# dimitar-schematic.net
KiCad netlist of a schematic drawn in EAGLE
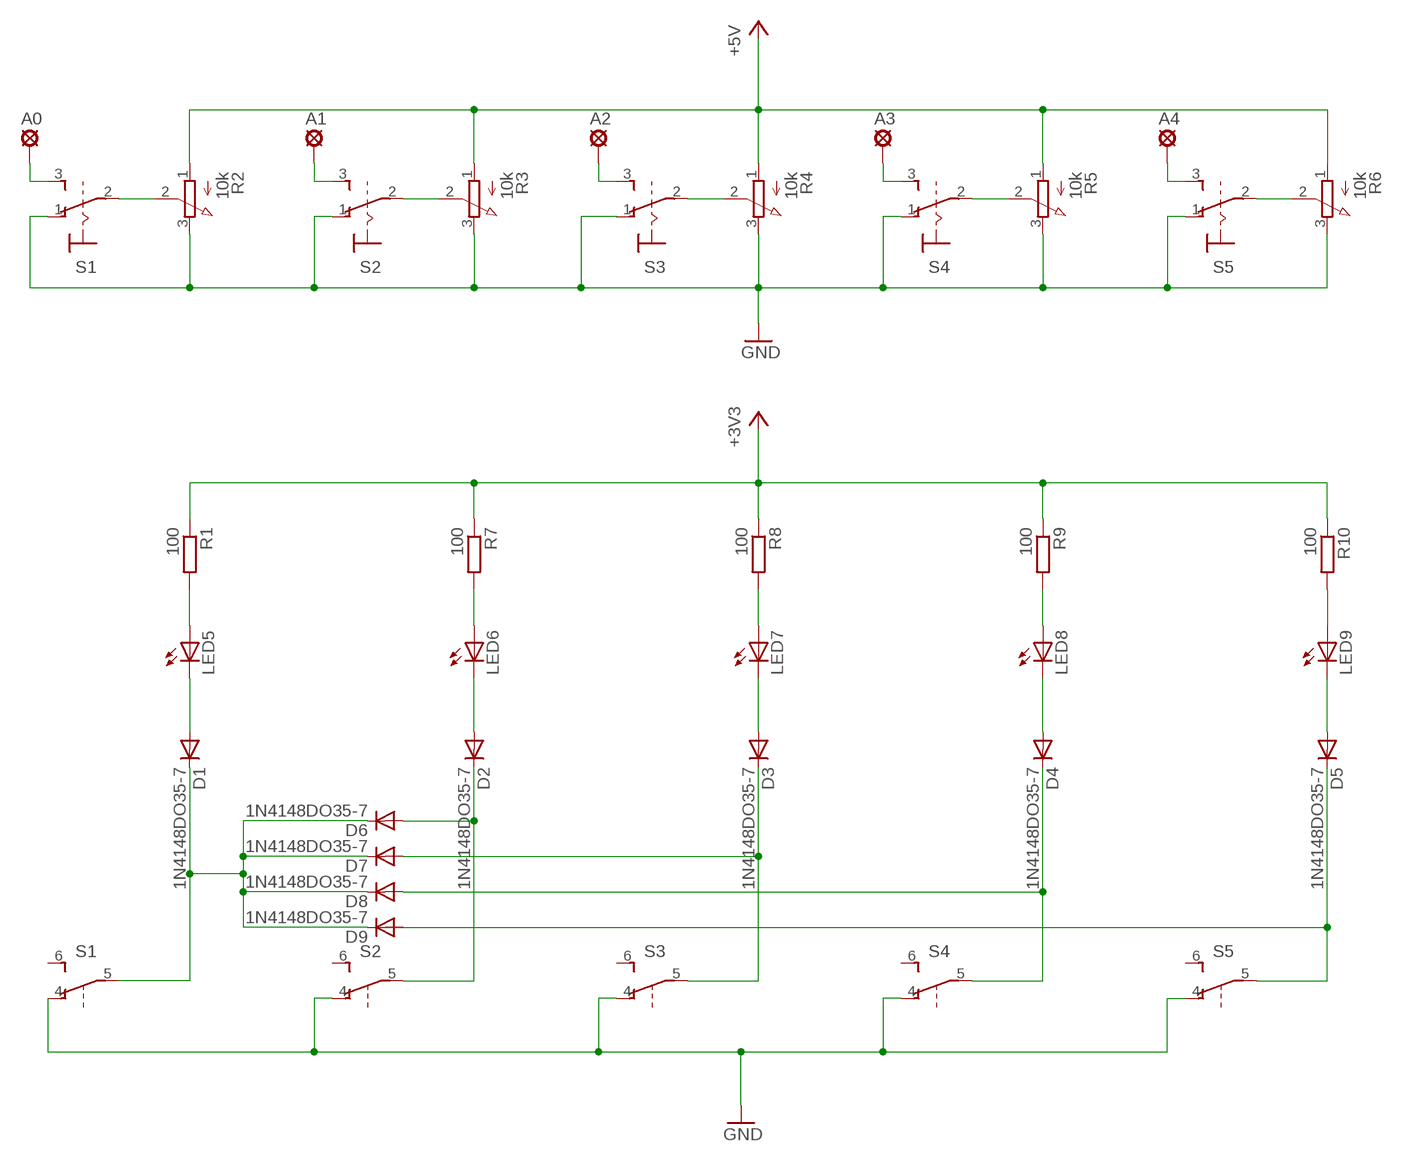
[diagram p0: schematic, sheet 1]

(export (version "E")
  (design (tool "Eeschema 10.0.6"))
  (components
    (comp (ref "A0")
      (value "SE14")
      (footprint "eagle-import:SE14")
      (libsource (lib "eagle-import") (part "SE14"))
    )
    (comp (ref "A1")
      (value "SE14")
      (footprint "eagle-import:SE14")
      (libsource (lib "eagle-import") (part "SE14"))
    )
    (comp (ref "A2")
      (value "SE14")
      (footprint "eagle-import:SE14")
      (libsource (lib "eagle-import") (part "SE14"))
    )
    (comp (ref "A3")
      (value "SE14")
      (footprint "eagle-import:SE14")
      (libsource (lib "eagle-import") (part "SE14"))
    )
    (comp (ref "A4")
      (value "SE14")
      (footprint "eagle-import:SE14")
      (libsource (lib "eagle-import") (part "SE14"))
    )
    (comp (ref "D1")
      (value "1N4148DO35-7")
      (footprint "eagle-import:DO35-7")
      (libsource (lib "eagle-import") (part "1N4148DO35-7"))
    )
    (comp (ref "D2")
      (value "1N4148DO35-7")
      (footprint "eagle-import:DO35-7")
      (libsource (lib "eagle-import") (part "1N4148DO35-7"))
    )
    (comp (ref "D3")
      (value "1N4148DO35-7")
      (footprint "eagle-import:DO35-7")
      (libsource (lib "eagle-import") (part "1N4148DO35-7"))
    )
    (comp (ref "D4")
      (value "1N4148DO35-7")
      (footprint "eagle-import:DO35-7")
      (libsource (lib "eagle-import") (part "1N4148DO35-7"))
    )
    (comp (ref "D5")
      (value "1N4148DO35-7")
      (footprint "eagle-import:DO35-7")
      (libsource (lib "eagle-import") (part "1N4148DO35-7"))
    )
    (comp (ref "D6")
      (value "1N4148DO35-7")
      (footprint "eagle-import:DO35-7")
      (libsource (lib "eagle-import") (part "1N4148DO35-7"))
    )
    (comp (ref "D7")
      (value "1N4148DO35-7")
      (footprint "eagle-import:DO35-7")
      (libsource (lib "eagle-import") (part "1N4148DO35-7"))
    )
    (comp (ref "D8")
      (value "1N4148DO35-7")
      (footprint "eagle-import:DO35-7")
      (libsource (lib "eagle-import") (part "1N4148DO35-7"))
    )
    (comp (ref "D9")
      (value "1N4148DO35-7")
      (footprint "eagle-import:DO35-7")
      (libsource (lib "eagle-import") (part "1N4148DO35-7"))
    )
    (comp (ref "LED5")
      (value "LED5MM")
      (footprint "eagle-import:LED5MM")
      (libsource (lib "eagle-import") (part "LED5MM"))
    )
    (comp (ref "LED6")
      (value "LED5MM")
      (footprint "eagle-import:LED5MM")
      (libsource (lib "eagle-import") (part "LED5MM"))
    )
    (comp (ref "LED7")
      (value "LED5MM")
      (footprint "eagle-import:LED5MM")
      (libsource (lib "eagle-import") (part "LED5MM"))
    )
    (comp (ref "LED8")
      (value "LED5MM")
      (footprint "eagle-import:LED5MM")
      (libsource (lib "eagle-import") (part "LED5MM"))
    )
    (comp (ref "LED9")
      (value "LED5MM")
      (footprint "eagle-import:LED5MM")
      (libsource (lib "eagle-import") (part "LED5MM"))
    )
    (comp (ref "R1")
      (value "100")
      (footprint "eagle-import:0207_10")
      (libsource (lib "eagle-import") (part "R0207/10"))
    )
    (comp (ref "R2")
      (value "10k")
      (footprint "eagle-import:3RP_1610N")
      (libsource (lib "eagle-import") (part "3RP/1610N"))
    )
    (comp (ref "R3")
      (value "10k")
      (footprint "eagle-import:3RP_1610N")
      (libsource (lib "eagle-import") (part "3RP/1610N"))
    )
    (comp (ref "R4")
      (value "10k")
      (footprint "eagle-import:3RP_1610N")
      (libsource (lib "eagle-import") (part "3RP/1610N"))
    )
    (comp (ref "R5")
      (value "10k")
      (footprint "eagle-import:3RP_1610N")
      (libsource (lib "eagle-import") (part "3RP/1610N"))
    )
    (comp (ref "R6")
      (value "10k")
      (footprint "eagle-import:3RP_1610N")
      (libsource (lib "eagle-import") (part "3RP/1610N"))
    )
    (comp (ref "R7")
      (value "100")
      (footprint "eagle-import:0207_10")
      (libsource (lib "eagle-import") (part "R0207/10"))
    )
    (comp (ref "R8")
      (value "100")
      (footprint "eagle-import:0207_10")
      (libsource (lib "eagle-import") (part "R0207/10"))
    )
    (comp (ref "R9")
      (value "100")
      (footprint "eagle-import:0207_10")
      (libsource (lib "eagle-import") (part "R0207/10"))
    )
    (comp (ref "R10")
      (value "100")
      (footprint "eagle-import:0207_10")
      (libsource (lib "eagle-import") (part "R0207/10"))
    )
    (comp (ref "S1")
      (value "320-938")
      (footprint "eagle-import:320-938")
      (libsource (lib "eagle-import") (part "320-938"))
    )
    (comp (ref "S2")
      (value "320-938")
      (footprint "eagle-import:320-938")
      (libsource (lib "eagle-import") (part "320-938"))
    )
    (comp (ref "S3")
      (value "320-938")
      (footprint "eagle-import:320-938")
      (libsource (lib "eagle-import") (part "320-938"))
    )
    (comp (ref "S4")
      (value "320-938")
      (footprint "eagle-import:320-938")
      (libsource (lib "eagle-import") (part "320-938"))
    )
    (comp (ref "S5")
      (value "320-938")
      (footprint "eagle-import:320-938")
      (libsource (lib "eagle-import") (part "320-938"))
    )
  )
  (nets
    (net (code "1") (name "+3V3") (class "Default")
      (node (ref "R1") (pin "1") (pinfunction "1_1") (pintype "passive"))
      (node (ref "R10") (pin "1") (pinfunction "1_1") (pintype "passive"))
      (node (ref "R7") (pin "1") (pinfunction "1_1") (pintype "passive"))
      (node (ref "R8") (pin "1") (pinfunction "1_1") (pintype "passive"))
      (node (ref "R9") (pin "1") (pinfunction "1_1") (pintype "passive"))
    )
    (net (code "2") (name "+5V") (class "Default")
      (node (ref "R2") (pin "1") (pinfunction "A_1") (pintype "passive"))
      (node (ref "R3") (pin "1") (pinfunction "A_1") (pintype "passive"))
      (node (ref "R4") (pin "1") (pinfunction "A_1") (pintype "passive"))
      (node (ref "R5") (pin "1") (pinfunction "A_1") (pintype "passive"))
      (node (ref "R6") (pin "1") (pinfunction "A_1") (pintype "passive"))
    )
    (net (code "3") (name "GND") (class "Default")
      (node (ref "R2") (pin "3") (pinfunction "E_3") (pintype "passive"))
      (node (ref "R3") (pin "3") (pinfunction "E_3") (pintype "passive"))
      (node (ref "R4") (pin "3") (pinfunction "E_3") (pintype "passive"))
      (node (ref "R5") (pin "3") (pinfunction "E_3") (pintype "passive"))
      (node (ref "R6") (pin "3") (pinfunction "E_3") (pintype "passive"))
      (node (ref "S1") (pin "1") (pinfunction "O_1") (pintype "passive"))
      (node (ref "S1") (pin "4") (pinfunction "O_4") (pintype "passive"))
      (node (ref "S2") (pin "1") (pinfunction "O_1") (pintype "passive"))
      (node (ref "S2") (pin "4") (pinfunction "O_4") (pintype "passive"))
      (node (ref "S3") (pin "1") (pinfunction "O_1") (pintype "passive"))
      (node (ref "S3") (pin "4") (pinfunction "O_4") (pintype "passive"))
      (node (ref "S4") (pin "1") (pinfunction "O_1") (pintype "passive"))
      (node (ref "S4") (pin "4") (pinfunction "O_4") (pintype "passive"))
      (node (ref "S5") (pin "1") (pinfunction "O_1") (pintype "passive"))
      (node (ref "S5") (pin "4") (pinfunction "O_4") (pintype "passive"))
    )
    (net (code "4") (name "Net-(LED5-C)") (class "Default")
      (node (ref "D1") (pin "A") (pinfunction "A_A") (pintype "passive"))
      (node (ref "LED5") (pin "K") (pinfunction "C_K") (pintype "passive"))
    )
    (net (code "5") (name "Net-(LED5-PadA)") (class "Default")
      (node (ref "LED5") (pin "A") (pinfunction "A_A") (pintype "passive"))
      (node (ref "R1") (pin "2") (pinfunction "2_2") (pintype "passive"))
    )
    (net (code "6") (name "Net-(LED6-C)") (class "Default")
      (node (ref "D2") (pin "A") (pinfunction "A_A") (pintype "passive"))
      (node (ref "LED6") (pin "K") (pinfunction "C_K") (pintype "passive"))
    )
    (net (code "7") (name "Net-(LED6-PadA)") (class "Default")
      (node (ref "LED6") (pin "A") (pinfunction "A_A") (pintype "passive"))
      (node (ref "R7") (pin "2") (pinfunction "2_2") (pintype "passive"))
    )
    (net (code "8") (name "Net-(LED7-C)") (class "Default")
      (node (ref "D3") (pin "A") (pinfunction "A_A") (pintype "passive"))
      (node (ref "LED7") (pin "K") (pinfunction "C_K") (pintype "passive"))
    )
    (net (code "9") (name "Net-(LED7-PadA)") (class "Default")
      (node (ref "LED7") (pin "A") (pinfunction "A_A") (pintype "passive"))
      (node (ref "R8") (pin "2") (pinfunction "2_2") (pintype "passive"))
    )
    (net (code "10") (name "Net-(LED8-C)") (class "Default")
      (node (ref "D4") (pin "A") (pinfunction "A_A") (pintype "passive"))
      (node (ref "LED8") (pin "K") (pinfunction "C_K") (pintype "passive"))
    )
    (net (code "11") (name "Net-(LED8-PadA)") (class "Default")
      (node (ref "LED8") (pin "A") (pinfunction "A_A") (pintype "passive"))
      (node (ref "R9") (pin "2") (pinfunction "2_2") (pintype "passive"))
    )
    (net (code "12") (name "Net-(LED9-C)") (class "Default")
      (node (ref "D5") (pin "A") (pinfunction "A_A") (pintype "passive"))
      (node (ref "LED9") (pin "K") (pinfunction "C_K") (pintype "passive"))
    )
    (net (code "13") (name "Net-(LED9-PadA)") (class "Default")
      (node (ref "LED9") (pin "A") (pinfunction "A_A") (pintype "passive"))
      (node (ref "R10") (pin "2") (pinfunction "2_2") (pintype "passive"))
    )
    (net (code "14") (name "Net-(R2-S)") (class "Default")
      (node (ref "R2") (pin "2") (pinfunction "S_2") (pintype "passive"))
      (node (ref "S1") (pin "2") (pinfunction "P_2") (pintype "passive"))
    )
    (net (code "15") (name "Net-(R3-S)") (class "Default")
      (node (ref "R3") (pin "2") (pinfunction "S_2") (pintype "passive"))
      (node (ref "S2") (pin "2") (pinfunction "P_2") (pintype "passive"))
    )
    (net (code "16") (name "Net-(R4-S)") (class "Default")
      (node (ref "R4") (pin "2") (pinfunction "S_2") (pintype "passive"))
      (node (ref "S3") (pin "2") (pinfunction "P_2") (pintype "passive"))
    )
    (net (code "17") (name "Net-(R5-S)") (class "Default")
      (node (ref "R5") (pin "2") (pinfunction "S_2") (pintype "passive"))
      (node (ref "S4") (pin "2") (pinfunction "P_2") (pintype "passive"))
    )
    (net (code "18") (name "Net-(R6-S)") (class "Default")
      (node (ref "R6") (pin "2") (pinfunction "S_2") (pintype "passive"))
      (node (ref "S5") (pin "2") (pinfunction "P_2") (pintype "passive"))
    )
    (net (code "19") (name "Net-(S1A-S)") (class "Default")
      (node (ref "A0") (pin "MP") (pinfunction "MP_MP") (pintype "passive"))
      (node (ref "S1") (pin "3") (pinfunction "S_3") (pintype "passive"))
    )
    (net (code "20") (name "Net-(S1B-P)") (class "Default")
      (node (ref "D1") (pin "C") (pinfunction "C_C") (pintype "passive"))
      (node (ref "D6") (pin "C") (pinfunction "C_C") (pintype "passive"))
      (node (ref "D7") (pin "C") (pinfunction "C_C") (pintype "passive"))
      (node (ref "D8") (pin "C") (pinfunction "C_C") (pintype "passive"))
      (node (ref "D9") (pin "C") (pinfunction "C_C") (pintype "passive"))
      (node (ref "S1") (pin "5") (pinfunction "P_5") (pintype "passive"))
    )
    (net (code "21") (name "Net-(S2A-S)") (class "Default")
      (node (ref "A1") (pin "MP") (pinfunction "MP_MP") (pintype "passive"))
      (node (ref "S2") (pin "3") (pinfunction "S_3") (pintype "passive"))
    )
    (net (code "22") (name "Net-(S2B-P)") (class "Default")
      (node (ref "D2") (pin "C") (pinfunction "C_C") (pintype "passive"))
      (node (ref "D6") (pin "A") (pinfunction "A_A") (pintype "passive"))
      (node (ref "S2") (pin "5") (pinfunction "P_5") (pintype "passive"))
    )
    (net (code "23") (name "Net-(S3A-S)") (class "Default")
      (node (ref "A2") (pin "MP") (pinfunction "MP_MP") (pintype "passive"))
      (node (ref "S3") (pin "3") (pinfunction "S_3") (pintype "passive"))
    )
    (net (code "24") (name "Net-(S3B-P)") (class "Default")
      (node (ref "D3") (pin "C") (pinfunction "C_C") (pintype "passive"))
      (node (ref "D7") (pin "A") (pinfunction "A_A") (pintype "passive"))
      (node (ref "S3") (pin "5") (pinfunction "P_5") (pintype "passive"))
    )
    (net (code "25") (name "Net-(S4A-S)") (class "Default")
      (node (ref "A3") (pin "MP") (pinfunction "MP_MP") (pintype "passive"))
      (node (ref "S4") (pin "3") (pinfunction "S_3") (pintype "passive"))
    )
    (net (code "26") (name "Net-(S4B-P)") (class "Default")
      (node (ref "D4") (pin "C") (pinfunction "C_C") (pintype "passive"))
      (node (ref "D8") (pin "A") (pinfunction "A_A") (pintype "passive"))
      (node (ref "S4") (pin "5") (pinfunction "P_5") (pintype "passive"))
    )
    (net (code "27") (name "Net-(S5A-S)") (class "Default")
      (node (ref "A4") (pin "MP") (pinfunction "MP_MP") (pintype "passive"))
      (node (ref "S5") (pin "3") (pinfunction "S_3") (pintype "passive"))
    )
    (net (code "28") (name "Net-(S5B-P)") (class "Default")
      (node (ref "D5") (pin "C") (pinfunction "C_C") (pintype "passive"))
      (node (ref "S5") (pin "5") (pinfunction "P_5") (pintype "passive"))
    )
    (net (code "29") (name "unconnected-(D9-PadA)") (class "Default")
      (node (ref "D9") (pin "A") (pinfunction "A_A") (pintype "passive"))
    )
    (net (code "30") (name "unconnected-(S1B-S-Pad6)") (class "Default")
      (node (ref "S1") (pin "6") (pinfunction "S_6") (pintype "passive"))
    )
    (net (code "31") (name "unconnected-(S2B-S-Pad6)") (class "Default")
      (node (ref "S2") (pin "6") (pinfunction "S_6") (pintype "passive"))
    )
    (net (code "32") (name "unconnected-(S3B-S-Pad6)") (class "Default")
      (node (ref "S3") (pin "6") (pinfunction "S_6") (pintype "passive"))
    )
    (net (code "33") (name "unconnected-(S4B-S-Pad6)") (class "Default")
      (node (ref "S4") (pin "6") (pinfunction "S_6") (pintype "passive"))
    )
    (net (code "34") (name "unconnected-(S5B-S-Pad6)") (class "Default")
      (node (ref "S5") (pin "6") (pinfunction "S_6") (pintype "passive"))
    )
  )
)
